# SCH_Device_2024-05-04.net
KiCad netlist of a schematic drawn in EasyEDA
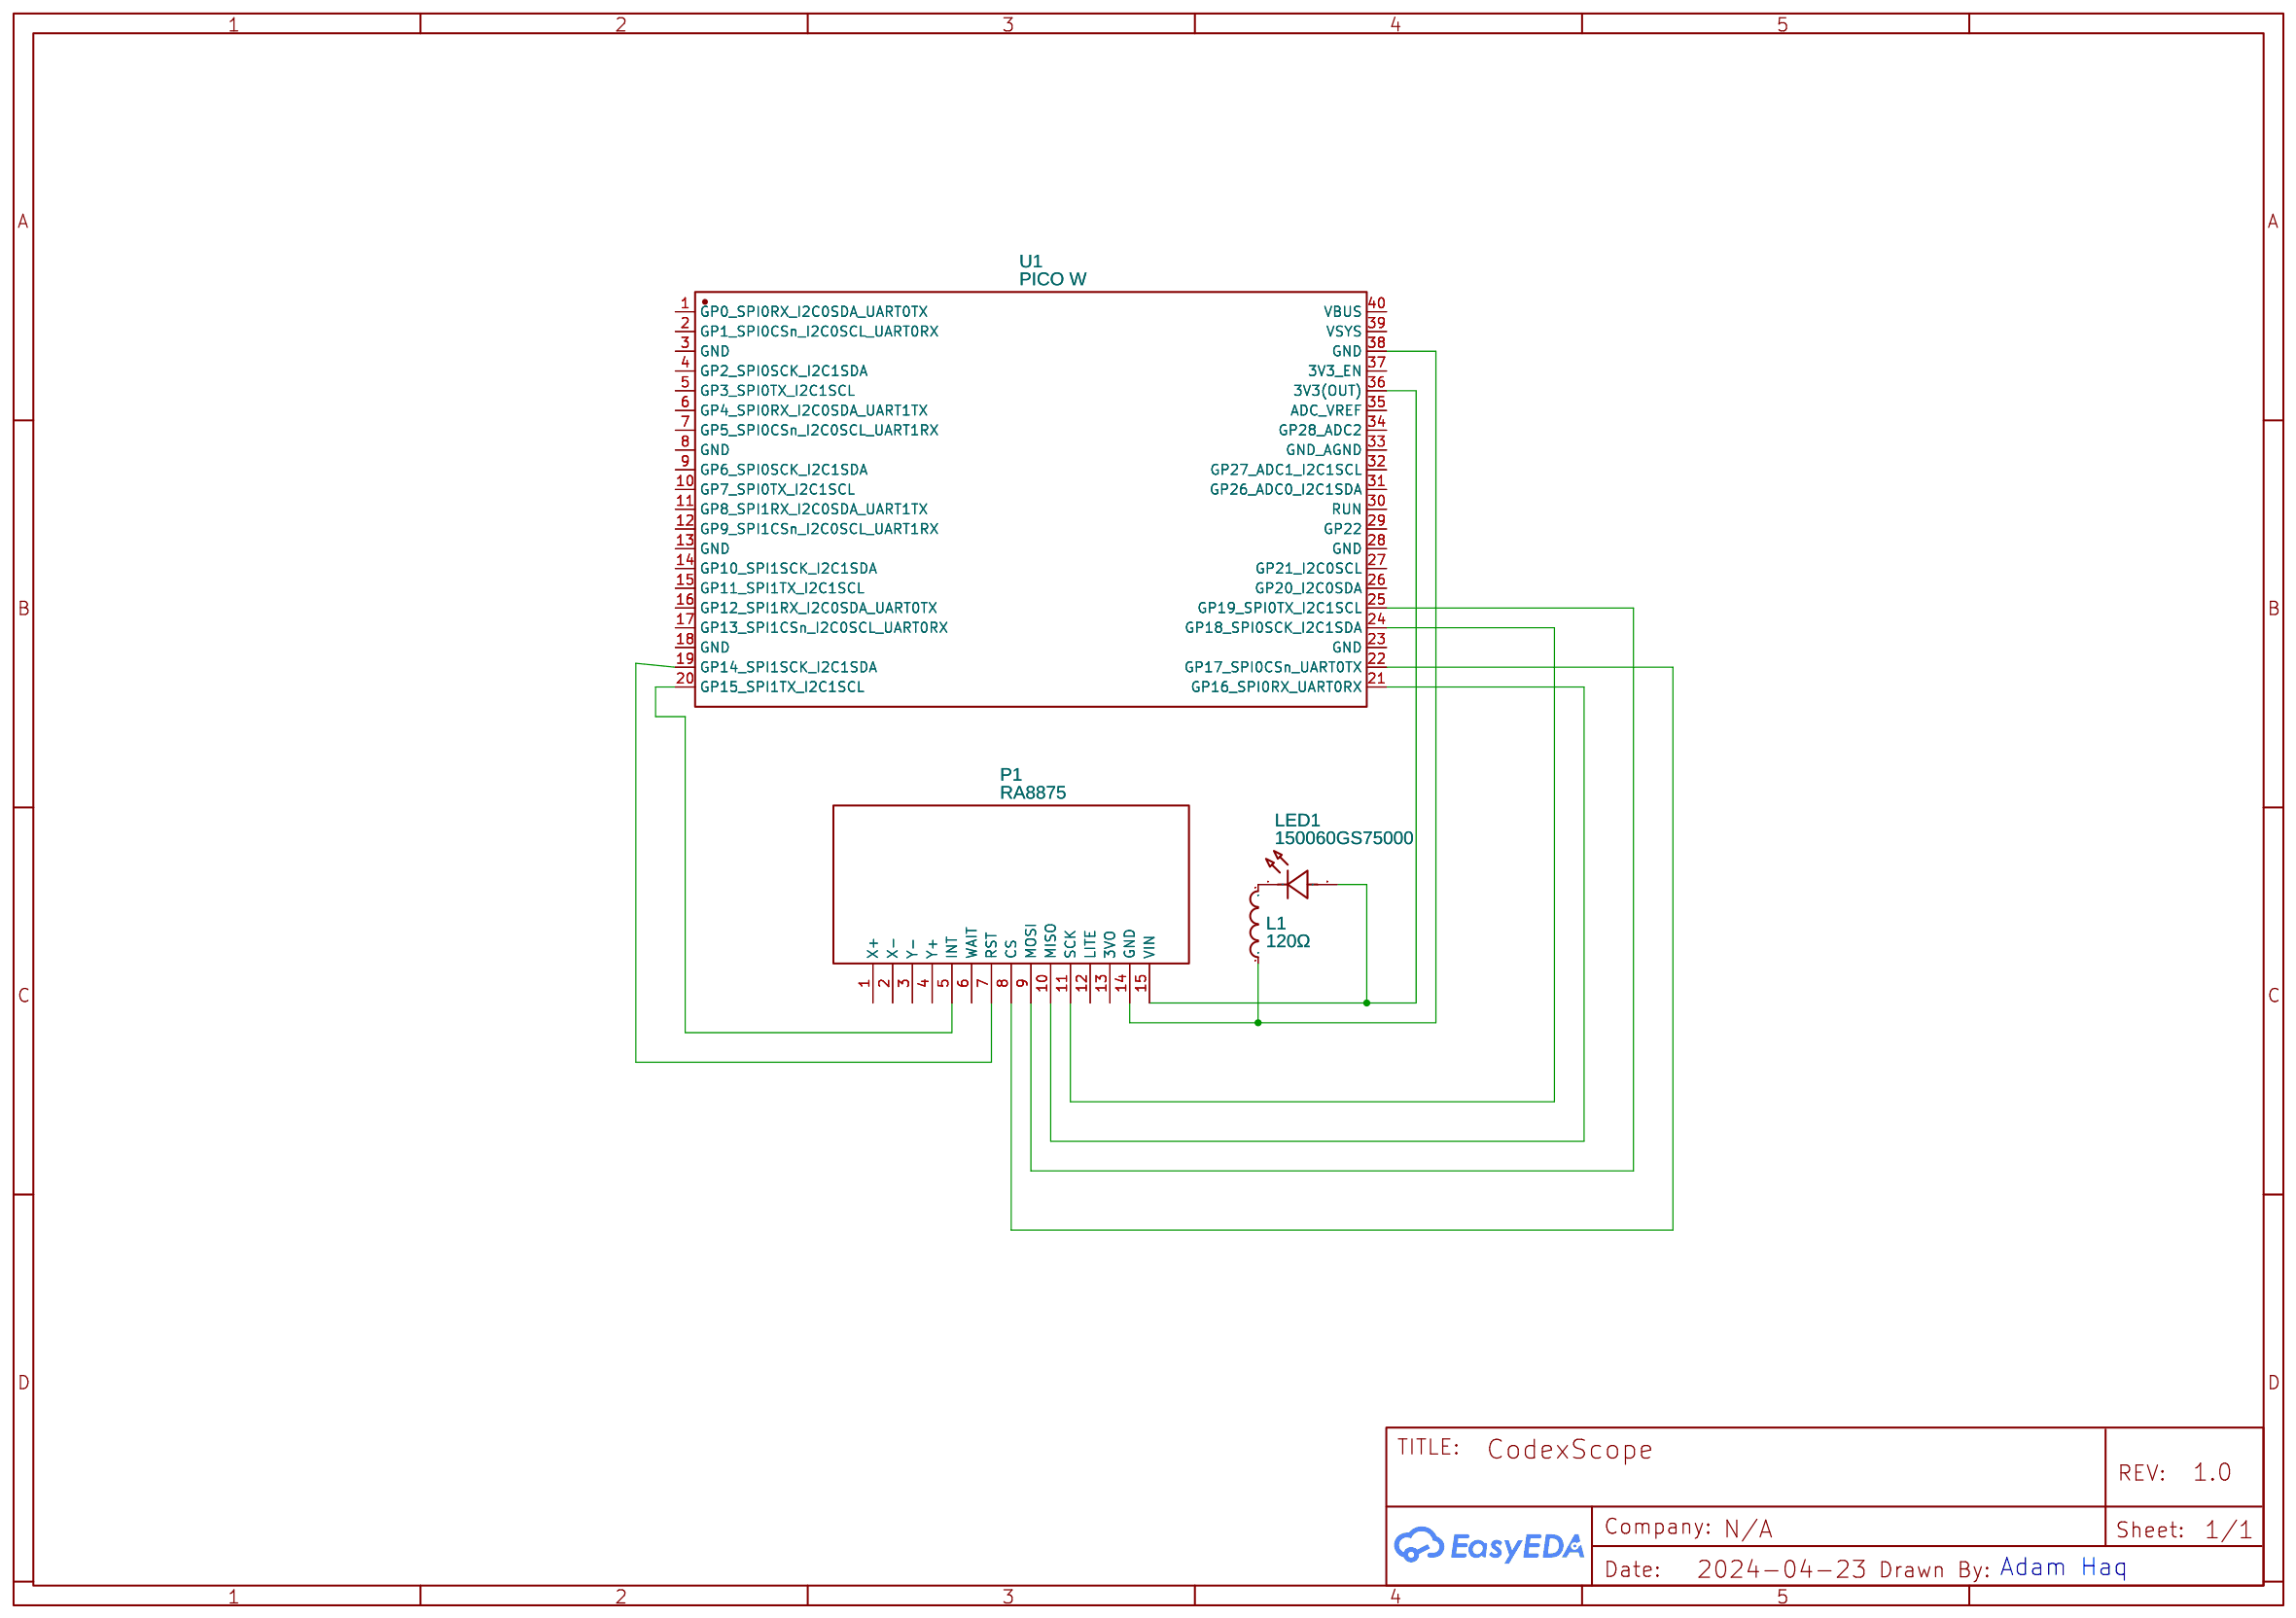
[diagram p0: schematic sheet]

(export (version "E")
  (design (tool "Eeschema 10.0.6"))
  (components
    (comp (ref "L1")
      (value "120Ω")
      (fields (field (name "Manufacturer Part") "MPZ1608S121ATAH0") (field (name "Manufacturer") "TDK"))
      (libsource (lib "") (part "MPZ1608S121ATAH0"))
    )
    (comp (ref "LED1")
      (value "150060GS75000")
      (fields (field (name "Manufacturer") "Wurth(伍尔特)"))
      (libsource (lib "") (part "150060GS75000"))
    )
    (comp (ref "P1") (value "RA8875") (libsource (lib "") (part "RA8875")))
    (comp (ref "U1")
      (value "PICO W")
      (fields (field (name "Manufacturer") "Raspberry Pi(树莓派)"))
      (libsource (lib "") (part "PICO W"))
    )
  )
  (nets
    (net (code "1") (name "Net-(LED1-A)") (class "Default")
      (node (ref "LED1") (pin "2") (pinfunction "A_2") (pintype "unspecified"))
      (node (ref "P1") (pin "15") (pinfunction "VIN_15") (pintype "unspecified"))
      (node (ref "U1") (pin "36") (pinfunction "3V3(OUT)_36") (pintype "unspecified"))
    )
    (net (code "2") (name "Net-(LED1-K)") (class "Default")
      (node (ref "L1") (pin "2") (pinfunction "2_2") (pintype "unspecified"))
      (node (ref "LED1") (pin "1") (pinfunction "K_1") (pintype "unspecified"))
    )
    (net (code "3") (name "Net-(P1-CS)") (class "Default")
      (node (ref "P1") (pin "8") (pinfunction "CS_8") (pintype "unspecified"))
      (node (ref "U1") (pin "22") (pinfunction "GP17_SPI0CSn_UART0TX_22") (pintype "unspecified"))
    )
    (net (code "4") (name "Net-(P1-GND)") (class "Default")
      (node (ref "L1") (pin "1") (pinfunction "1_1") (pintype "unspecified"))
      (node (ref "P1") (pin "14") (pinfunction "GND_14") (pintype "unspecified"))
      (node (ref "U1") (pin "38") (pinfunction "GND_38") (pintype "unspecified"))
    )
    (net (code "5") (name "Net-(P1-INT)") (class "Default")
      (node (ref "P1") (pin "5") (pinfunction "INT_5") (pintype "unspecified"))
      (node (ref "U1") (pin "20") (pinfunction "GP15_SPI1TX_I2C1SCL_20") (pintype "unspecified"))
    )
    (net (code "6") (name "Net-(P1-MISO)") (class "Default")
      (node (ref "P1") (pin "10") (pinfunction "MISO_10") (pintype "unspecified"))
      (node (ref "U1") (pin "21") (pinfunction "GP16_SPI0RX_UART0RX_21") (pintype "unspecified"))
    )
    (net (code "7") (name "Net-(P1-MOSI)") (class "Default")
      (node (ref "P1") (pin "9") (pinfunction "MOSI_9") (pintype "unspecified"))
      (node (ref "U1") (pin "25") (pinfunction "GP19_SPI0TX_I2C1SCL_25") (pintype "unspecified"))
    )
    (net (code "8") (name "Net-(P1-RST)") (class "Default")
      (node (ref "P1") (pin "7") (pinfunction "RST_7") (pintype "unspecified"))
      (node (ref "U1") (pin "19") (pinfunction "GP14_SPI1SCK_I2C1SDA_19") (pintype "unspecified"))
    )
    (net (code "9") (name "Net-(P1-SCK)") (class "Default")
      (node (ref "P1") (pin "11") (pinfunction "SCK_11") (pintype "unspecified"))
      (node (ref "U1") (pin "24") (pinfunction "GP18_SPI0SCK_I2C1SDA_24") (pintype "unspecified"))
    )
    (net (code "10") (name "unconnected-(P1-3VO-Pad13)") (class "Default")
      (node (ref "P1") (pin "13") (pinfunction "3VO_13") (pintype "unspecified"))
    )
    (net (code "11") (name "unconnected-(P1-LITE-Pad12)") (class "Default")
      (node (ref "P1") (pin "12") (pinfunction "LITE_12") (pintype "unspecified"))
    )
    (net (code "12") (name "unconnected-(P1-WAIT-Pad6)") (class "Default")
      (node (ref "P1") (pin "6") (pinfunction "WAIT_6") (pintype "unspecified"))
    )
    (net (code "13") (name "unconnected-(P1-X+-Pad1)") (class "Default")
      (node (ref "P1") (pin "1") (pinfunction "X+_1") (pintype "unspecified"))
    )
    (net (code "14") (name "unconnected-(P1-X--Pad2)") (class "Default")
      (node (ref "P1") (pin "2") (pinfunction "X-_2") (pintype "unspecified"))
    )
    (net (code "15") (name "unconnected-(P1-Y+-Pad4)") (class "Default")
      (node (ref "P1") (pin "4") (pinfunction "Y+_4") (pintype "unspecified"))
    )
    (net (code "16") (name "unconnected-(P1-Y--Pad3)") (class "Default")
      (node (ref "P1") (pin "3") (pinfunction "Y-_3") (pintype "unspecified"))
    )
    (net (code "17") (name "unconnected-(U1-3V3_EN-Pad37)") (class "Default")
      (node (ref "U1") (pin "37") (pinfunction "3V3_EN_37") (pintype "unspecified"))
    )
    (net (code "18") (name "unconnected-(U1-ADC_VREF-Pad35)") (class "Default")
      (node (ref "U1") (pin "35") (pinfunction "ADC_VREF_35") (pintype "unspecified"))
    )
    (net (code "19") (name "unconnected-(U1-GND-Pad3)") (class "Default")
      (node (ref "U1") (pin "3") (pinfunction "GND_3") (pintype "unspecified"))
    )
    (net (code "20") (name "unconnected-(U1-GND-Pad8)") (class "Default")
      (node (ref "U1") (pin "8") (pinfunction "GND_8") (pintype "unspecified"))
    )
    (net (code "21") (name "unconnected-(U1-GND-Pad13)") (class "Default")
      (node (ref "U1") (pin "13") (pinfunction "GND_13") (pintype "unspecified"))
    )
    (net (code "22") (name "unconnected-(U1-GND-Pad18)") (class "Default")
      (node (ref "U1") (pin "18") (pinfunction "GND_18") (pintype "unspecified"))
    )
    (net (code "23") (name "unconnected-(U1-GND-Pad23)") (class "Default")
      (node (ref "U1") (pin "23") (pinfunction "GND_23") (pintype "unspecified"))
    )
    (net (code "24") (name "unconnected-(U1-GND-Pad28)") (class "Default")
      (node (ref "U1") (pin "28") (pinfunction "GND_28") (pintype "unspecified"))
    )
    (net (code "25") (name "unconnected-(U1-GND_AGND-Pad33)") (class "Default")
      (node (ref "U1") (pin "33") (pinfunction "GND_AGND_33") (pintype "unspecified"))
    )
    (net (code "26") (name "unconnected-(U1-GP0_SPI0RX_I2C0SDA_UART0TX-Pad1)") (class "Default")
      (node (ref "U1") (pin "1") (pinfunction "GP0_SPI0RX_I2C0SDA_UART0TX_1") (pintype "unspecified"))
    )
    (net (code "27") (name "unconnected-(U1-GP1_SPI0CSn_I2C0SCL_UART0RX-Pad2)") (class "Default")
      (node (ref "U1") (pin "2") (pinfunction "GP1_SPI0CSn_I2C0SCL_UART0RX_2") (pintype "unspecified"))
    )
    (net (code "28") (name "unconnected-(U1-GP2_SPI0SCK_I2C1SDA-Pad4)") (class "Default")
      (node (ref "U1") (pin "4") (pinfunction "GP2_SPI0SCK_I2C1SDA_4") (pintype "unspecified"))
    )
    (net (code "29") (name "unconnected-(U1-GP3_SPI0TX_I2C1SCL-Pad5)") (class "Default")
      (node (ref "U1") (pin "5") (pinfunction "GP3_SPI0TX_I2C1SCL_5") (pintype "unspecified"))
    )
    (net (code "30") (name "unconnected-(U1-GP4_SPI0RX_I2C0SDA_UART1TX-Pad6)") (class "Default")
      (node (ref "U1") (pin "6") (pinfunction "GP4_SPI0RX_I2C0SDA_UART1TX_6") (pintype "unspecified"))
    )
    (net (code "31") (name "unconnected-(U1-GP5_SPI0CSn_I2C0SCL_UART1RX-Pad7)") (class "Default")
      (node (ref "U1") (pin "7") (pinfunction "GP5_SPI0CSn_I2C0SCL_UART1RX_7") (pintype "unspecified"))
    )
    (net (code "32") (name "unconnected-(U1-GP6_SPI0SCK_I2C1SDA-Pad9)") (class "Default")
      (node (ref "U1") (pin "9") (pinfunction "GP6_SPI0SCK_I2C1SDA_9") (pintype "unspecified"))
    )
    (net (code "33") (name "unconnected-(U1-GP7_SPI0TX_I2C1SCL-Pad10)") (class "Default")
      (node (ref "U1") (pin "10") (pinfunction "GP7_SPI0TX_I2C1SCL_10") (pintype "unspecified"))
    )
    (net (code "34") (name "unconnected-(U1-GP8_SPI1RX_I2C0SDA_UART1TX-Pad11)") (class "Default")
      (node (ref "U1") (pin "11") (pinfunction "GP8_SPI1RX_I2C0SDA_UART1TX_11") (pintype "unspecified"))
    )
    (net (code "35") (name "unconnected-(U1-GP9_SPI1CSn_I2C0SCL_UART1RX-Pad12)") (class "Default")
      (node (ref "U1") (pin "12") (pinfunction "GP9_SPI1CSn_I2C0SCL_UART1RX_12") (pintype "unspecified"))
    )
    (net (code "36") (name "unconnected-(U1-GP10_SPI1SCK_I2C1SDA-Pad14)") (class "Default")
      (node (ref "U1") (pin "14") (pinfunction "GP10_SPI1SCK_I2C1SDA_14") (pintype "unspecified"))
    )
    (net (code "37") (name "unconnected-(U1-GP11_SPI1TX_I2C1SCL-Pad15)") (class "Default")
      (node (ref "U1") (pin "15") (pinfunction "GP11_SPI1TX_I2C1SCL_15") (pintype "unspecified"))
    )
    (net (code "38") (name "unconnected-(U1-GP12_SPI1RX_I2C0SDA_UART0TX-Pad16)") (class "Default")
      (node (ref "U1") (pin "16") (pinfunction "GP12_SPI1RX_I2C0SDA_UART0TX_16") (pintype "unspecified"))
    )
    (net (code "39") (name "unconnected-(U1-GP13_SPI1CSn_I2C0SCL_UART0RX-Pad17)") (class "Default")
      (node (ref "U1") (pin "17") (pinfunction "GP13_SPI1CSn_I2C0SCL_UART0RX_17") (pintype "unspecified"))
    )
    (net (code "40") (name "unconnected-(U1-GP20_I2C0SDA-Pad26)") (class "Default")
      (node (ref "U1") (pin "26") (pinfunction "GP20_I2C0SDA_26") (pintype "unspecified"))
    )
    (net (code "41") (name "unconnected-(U1-GP21_I2C0SCL-Pad27)") (class "Default")
      (node (ref "U1") (pin "27") (pinfunction "GP21_I2C0SCL_27") (pintype "unspecified"))
    )
    (net (code "42") (name "unconnected-(U1-GP22-Pad29)") (class "Default")
      (node (ref "U1") (pin "29") (pinfunction "GP22_29") (pintype "unspecified"))
    )
    (net (code "43") (name "unconnected-(U1-GP26_ADC0_I2C1SDA-Pad31)") (class "Default")
      (node (ref "U1") (pin "31") (pinfunction "GP26_ADC0_I2C1SDA_31") (pintype "unspecified"))
    )
    (net (code "44") (name "unconnected-(U1-GP27_ADC1_I2C1SCL-Pad32)") (class "Default")
      (node (ref "U1") (pin "32") (pinfunction "GP27_ADC1_I2C1SCL_32") (pintype "unspecified"))
    )
    (net (code "45") (name "unconnected-(U1-GP28_ADC2-Pad34)") (class "Default")
      (node (ref "U1") (pin "34") (pinfunction "GP28_ADC2_34") (pintype "unspecified"))
    )
    (net (code "46") (name "unconnected-(U1-RUN-Pad30)") (class "Default")
      (node (ref "U1") (pin "30") (pinfunction "RUN_30") (pintype "unspecified"))
    )
    (net (code "47") (name "unconnected-(U1-VBUS-Pad40)") (class "Default")
      (node (ref "U1") (pin "40") (pinfunction "VBUS_40") (pintype "unspecified"))
    )
    (net (code "48") (name "unconnected-(U1-VSYS-Pad39)") (class "Default")
      (node (ref "U1") (pin "39") (pinfunction "VSYS_39") (pintype "unspecified"))
    )
  )
)
